# JacdacRgbLedRing8_37.net
KiCad netlist of a schematic drawn in Altium Designer
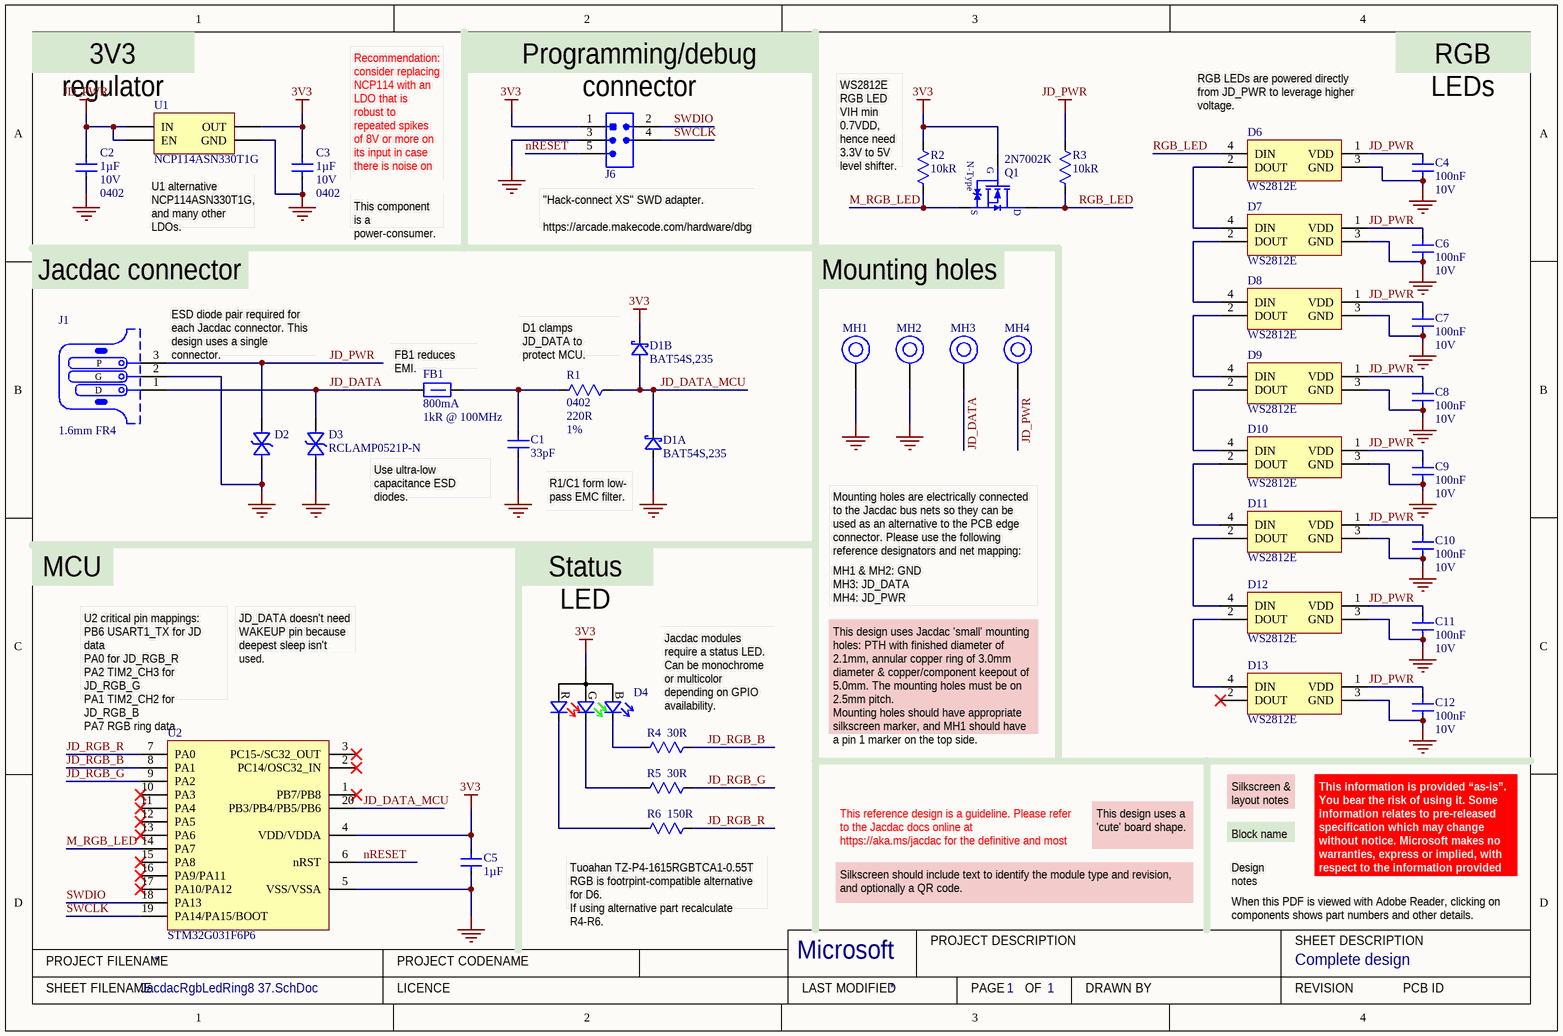
[diagram p0: JacdacRgbLedRing8 37.SchDoc]

(export (version "E")
  (design (tool "Eeschema 10.0.6"))
  (components
    (comp (ref "C1")
      (value "CL05C330JB51PNC")
      (footprint "C0402_0.55MM - without outline")
      (description "CAP CER 33PF 50V NP0 0402")
      (fields
        (field (name "MANUFACTURER") "Samsung")
        (field (name "TOLERANCE") "5%")
        (field (name "CAPACITANCE") "33pF")
        (field (name "CHECKED") "?")
        (field (name "CREATED") "DG")
      )
      (libsource (lib "Samsung") (part "CL05C330JB51PNC"))
    )
    (comp (ref "C2")
      (value "CL05A105KP5NNNC")
      (footprint "C0402_0.55MM - without outline")
      (description "CAP CER 1UF 10V X5R 0402")
      (fields
        (field (name "MANUFACTURER") "Samsung")
        (field (name "TOLERANCE") "10%")
        (field (name "CAPACITANCE") "1µF")
        (field (name "VOLTAGE RATING") "10V")
        (field (name "CASE CODE (IMPERIAL)") "0402")
        (field (name "CREATED") "DG")
        (field (name "CHECKED") "?")
      )
      (libsource (lib "Samsung") (part "CL05A105KP5NNNC"))
    )
    (comp (ref "C3")
      (value "CL05A105KP5NNNC")
      (footprint "C0402_0.55MM - without outline")
      (description "CAP CER 1UF 10V X5R 0402")
      (fields
        (field (name "MANUFACTURER") "Samsung")
        (field (name "TOLERANCE") "10%")
        (field (name "CAPACITANCE") "1µF")
        (field (name "VOLTAGE RATING") "10V")
        (field (name "CASE CODE (IMPERIAL)") "0402")
        (field (name "CREATED") "DG")
        (field (name "CHECKED") "?")
      )
      (libsource (lib "Samsung") (part "CL05A105KP5NNNC"))
    )
    (comp (ref "C4")
      (value "CL05B104KP5NNNC")
      (footprint "C0402_0.55MM - without outline")
      (description "CAP CER 0.1UF 10V X7R 0402")
      (fields
        (field (name "MANUFACTURER") "Samsung")
        (field (name "CAPACITANCE") "100nF")
        (field (name "TOLERANCE") "10%")
        (field (name "VOLTAGE RATING") "10V")
        (field (name "CREATED") "DG")
        (field (name "CHECKED") "?")
      )
      (libsource (lib "Samsung") (part "CL05B104KP5NNNC"))
    )
    (comp (ref "C5")
      (value "CL05A105KP5NNNC")
      (footprint "C0402_0.55MM - without outline")
      (description "CAP CER 1UF 10V X5R 0402")
      (fields
        (field (name "MANUFACTURER") "Samsung")
        (field (name "TOLERANCE") "10%")
        (field (name "CAPACITANCE") "1µF")
        (field (name "CREATED") "DG")
        (field (name "CHECKED") "?")
      )
      (libsource (lib "Samsung") (part "CL05A105KP5NNNC"))
    )
    (comp (ref "C6")
      (value "CL05B104KP5NNNC")
      (footprint "C0402_0.55MM - without outline")
      (description "CAP CER 0.1UF 10V X7R 0402")
      (fields
        (field (name "MANUFACTURER") "Samsung")
        (field (name "CAPACITANCE") "100nF")
        (field (name "TOLERANCE") "10%")
        (field (name "VOLTAGE RATING") "10V")
        (field (name "CREATED") "DG")
        (field (name "CHECKED") "?")
      )
      (libsource (lib "Samsung") (part "CL05B104KP5NNNC"))
    )
    (comp (ref "C7")
      (value "CL05B104KP5NNNC")
      (footprint "C0402_0.55MM - without outline")
      (description "CAP CER 0.1UF 10V X7R 0402")
      (fields
        (field (name "MANUFACTURER") "Samsung")
        (field (name "CAPACITANCE") "100nF")
        (field (name "TOLERANCE") "10%")
        (field (name "VOLTAGE RATING") "10V")
        (field (name "CREATED") "DG")
        (field (name "CHECKED") "?")
      )
      (libsource (lib "Samsung") (part "CL05B104KP5NNNC"))
    )
    (comp (ref "C8")
      (value "CL05B104KP5NNNC")
      (footprint "C0402_0.55MM - without outline")
      (description "CAP CER 0.1UF 10V X7R 0402")
      (fields
        (field (name "MANUFACTURER") "Samsung")
        (field (name "CAPACITANCE") "100nF")
        (field (name "TOLERANCE") "10%")
        (field (name "VOLTAGE RATING") "10V")
        (field (name "CREATED") "DG")
        (field (name "CHECKED") "?")
      )
      (libsource (lib "Samsung") (part "CL05B104KP5NNNC"))
    )
    (comp (ref "C9")
      (value "CL05B104KP5NNNC")
      (footprint "C0402_0.55MM - without outline")
      (description "CAP CER 0.1UF 10V X7R 0402")
      (fields
        (field (name "MANUFACTURER") "Samsung")
        (field (name "CAPACITANCE") "100nF")
        (field (name "TOLERANCE") "10%")
        (field (name "VOLTAGE RATING") "10V")
        (field (name "CREATED") "DG")
        (field (name "CHECKED") "?")
      )
      (libsource (lib "Samsung") (part "CL05B104KP5NNNC"))
    )
    (comp (ref "C10")
      (value "CL05B104KP5NNNC")
      (footprint "C0402_0.55MM - without outline")
      (description "CAP CER 0.1UF 10V X7R 0402")
      (fields
        (field (name "MANUFACTURER") "Samsung")
        (field (name "CAPACITANCE") "100nF")
        (field (name "TOLERANCE") "10%")
        (field (name "VOLTAGE RATING") "10V")
        (field (name "CREATED") "DG")
        (field (name "CHECKED") "?")
      )
      (libsource (lib "Samsung") (part "CL05B104KP5NNNC"))
    )
    (comp (ref "C11")
      (value "CL05B104KP5NNNC")
      (footprint "C0402_0.55MM - without outline")
      (description "CAP CER 0.1UF 10V X7R 0402")
      (fields
        (field (name "MANUFACTURER") "Samsung")
        (field (name "CAPACITANCE") "100nF")
        (field (name "TOLERANCE") "10%")
        (field (name "VOLTAGE RATING") "10V")
        (field (name "CREATED") "DG")
        (field (name "CHECKED") "?")
      )
      (libsource (lib "Samsung") (part "CL05B104KP5NNNC"))
    )
    (comp (ref "C12")
      (value "CL05B104KP5NNNC")
      (footprint "C0402_0.55MM - without outline")
      (description "CAP CER 0.1UF 10V X7R 0402")
      (fields
        (field (name "MANUFACTURER") "Samsung")
        (field (name "CAPACITANCE") "100nF")
        (field (name "TOLERANCE") "10%")
        (field (name "VOLTAGE RATING") "10V")
        (field (name "CREATED") "DG")
        (field (name "CHECKED") "?")
      )
      (libsource (lib "Samsung") (part "CL05B104KP5NNNC"))
    )
    (comp (ref "D1")
      (value "BAT54S")
      (footprint "NXP-BAT54S-TO-236AB - without outline")
      (description "DIODE ARRAY SCHOTTKY 30V SOT23")
      (fields (field (name "MANUFACTURER") "Nexperia") (field (name "MANUFACTURER PART NUMBER") "BAT54S,235"))
      (libsource (lib "NXP") (part "BAT54S"))
    )
    (comp (ref "D2")
      (value "RCLAMP0521P-N")
      (footprint "TVS 0402 - L")
      (description "Bidirectional 5V (Max) 6V 16V 3.5A (8/20us) 0402 TVS RoHS")
      (fields
        (field (name "MANUFACTURER") "Born Semiconductor")
        (field (name "CREATED BY") "D Gakure")
        (field (name "CHECKED BY") "?")
      )
      (libsource (lib "BornSemiconductor") (part "RCLAMP0521P-N"))
    )
    (comp (ref "D3")
      (value "RCLAMP0521P-N")
      (footprint "TVS 0402 - L")
      (description "Bidirectional 5V (Max) 6V 16V 3.5A (8/20us) 0402 TVS RoHS")
      (fields
        (field (name "MANUFACTURER") "Born Semiconductor")
        (field (name "MANUFACTURER PART NUMBER") "RCLAMP0521P-N")
        (field (name "CREATED BY") "D Gakure")
        (field (name "CHECKED BY") "?")
      )
      (libsource (lib "BornSemiconductor") (part "RCLAMP0521P-N"))
    )
    (comp (ref "D4")
      (value "TZ-P4-1615RGBTCA1-0.55T")
      (footprint "TZ-P4-1615RGBTCA1-0.55T")
      (description "1615 Light Emitting Diodes (LED) RoHS")
      (fields
        (field (name "MANUFACTURER") "TUOZHAN")
        (field (name "CREATED BY") "D. Gakure")
        (field (name "CHECKED BY") "?")
      )
      (libsource (lib "Tuozhan") (part "TZ-P4-1615RGBTCA1-0.55T"))
    )
    (comp (ref "D6")
      (value "WS2812E")
      (footprint "WS2812E-5050")
      (description "WS2812E 5050 RGB LED WITH INTEGRATED DRIVER")
      (fields (field (name "MANUFACTURER") "Worldsemi") (field (name "MANUFACTURER PART NUMBER") "WS2812E"))
      (libsource (lib "WorldSemi") (part "WS2812E-5050"))
    )
    (comp (ref "D7")
      (value "WS2812E")
      (footprint "WS2812E-5050")
      (description "WS2812E 5050 RGB LED WITH INTEGRATED DRIVER")
      (fields (field (name "MANUFACTURER") "Worldsemi") (field (name "MANUFACTURER PART NUMBER") "WS2812E"))
      (libsource (lib "WorldSemi") (part "WS2812E-5050"))
    )
    (comp (ref "D8")
      (value "WS2812E")
      (footprint "WS2812E-5050")
      (description "WS2812E 5050 RGB LED WITH INTEGRATED DRIVER")
      (fields (field (name "MANUFACTURER") "Worldsemi") (field (name "MANUFACTURER PART NUMBER") "WS2812E"))
      (libsource (lib "WorldSemi") (part "WS2812E-5050"))
    )
    (comp (ref "D9")
      (value "WS2812E")
      (footprint "WS2812E-5050")
      (description "WS2812E 5050 RGB LED WITH INTEGRATED DRIVER")
      (fields (field (name "MANUFACTURER") "Worldsemi") (field (name "MANUFACTURER PART NUMBER") "WS2812E"))
      (libsource (lib "WorldSemi") (part "WS2812E-5050"))
    )
    (comp (ref "D10")
      (value "WS2812E")
      (footprint "WS2812E-5050")
      (description "WS2812E 5050 RGB LED WITH INTEGRATED DRIVER")
      (fields (field (name "MANUFACTURER") "Worldsemi") (field (name "MANUFACTURER PART NUMBER") "WS2812E"))
      (libsource (lib "WorldSemi") (part "WS2812E-5050"))
    )
    (comp (ref "D11")
      (value "WS2812E")
      (footprint "WS2812E-5050")
      (description "WS2812E 5050 RGB LED WITH INTEGRATED DRIVER")
      (fields (field (name "MANUFACTURER") "Worldsemi") (field (name "MANUFACTURER PART NUMBER") "WS2812E"))
      (libsource (lib "WorldSemi") (part "WS2812E-5050"))
    )
    (comp (ref "D12")
      (value "WS2812E")
      (footprint "WS2812E-5050")
      (description "WS2812E 5050 RGB LED WITH INTEGRATED DRIVER")
      (fields (field (name "MANUFACTURER") "Worldsemi") (field (name "MANUFACTURER PART NUMBER") "WS2812E"))
      (libsource (lib "WorldSemi") (part "WS2812E-5050"))
    )
    (comp (ref "D13")
      (value "WS2812E")
      (footprint "WS2812E-5050")
      (description "WS2812E 5050 RGB LED WITH INTEGRATED DRIVER")
      (fields (field (name "MANUFACTURER") "Worldsemi") (field (name "MANUFACTURER PART NUMBER") "WS2812E"))
      (libsource (lib "WorldSemi") (part "WS2812E-5050"))
    )
    (comp (ref "FB1")
      (value "TDK MPZ1608S102ATA00")
      (footprint "TDK MPZ1608 0.8mm - without outline")
      (description "0603 1k@100MHz 0.8A chip")
      (fields
        (field (name "TOLERANCE") "25%")
        (field (name "MANUFACTURER") "TDK")
        (field (name "CURRENT RATING") "800mA")
        (field (name "IMPEDANCE") "1kR @ 100MHz")
      )
      (libsource (lib "TDK") (part "TDK MPZ1608S102ATA00"))
    )
    (comp (ref "J1")
      (value "3 pin JACDAC edge connector")
      (footprint "JACDAC_EDGE_CONNECTOR_NO_TRACES")
      (description "3 pin Jacdac edge connector 1.27mm pitch")
      (fields
        (field (name "MANUFACTURER PART NUMBER") "JACDAC_EDGE_CONNECTOR")
        (field (name "PCB TYPE") "1.6mm FR4")
        (field (name "CHECKED BY") "?")
        (field (name "CREATED BY") "D. Gakure")
      )
      (libsource (lib "generic-con") (part "Jacdac edge connector"))
    )
    (comp (ref "J6")
      (value "Hack Connect Mini 1.27 mm pitch 2-row")
      (footprint "HACK_CONNECT_MINI_5_X_1_27")
      (libsource (lib "HackConnect") (part "HACK_CONNECT_MINI"))
    )
    (comp (ref "MH1")
      (value "MH_5.0MMK_3.0MMC_2.1MMD_PTH")
      (footprint "MH_5.0MMK_3.0MMC_2.1MMD_PTH:MH_5.0MMK_3.0MMC_2.1MMD_PTH")
      (description "Mounting Hole 5.0mm keepout, 3.0mm annualar ring and 2.1mm Drill PTH")
      (libsource (lib "generic") (part "MH_5.0MMK_3.0MMC_2.1MMD_PTH"))
    )
    (comp (ref "MH2")
      (value "MH_5.0MMK_3.0MMC_2.1MMD_PTH")
      (footprint "MH_5.0MMK_3.0MMC_2.1MMD_PTH:MH_5.0MMK_3.0MMC_2.1MMD_PTH")
      (description "Mounting Hole 5.0mm keepout, 3.0mm annualar ring and 2.1mm Drill PTH")
      (libsource (lib "generic") (part "MH_5.0MMK_3.0MMC_2.1MMD_PTH"))
    )
    (comp (ref "MH3")
      (value "MH_5.0MMK_3.0MMC_2.1MMD_PTH")
      (footprint "MH_5.0MMK_3.0MMC_2.1MMD_PTH:MH_5.0MMK_3.0MMC_2.1MMD_PTH")
      (description "Mounting Hole 5.0mm keepout, 3.0mm annualar ring and 2.1mm Drill PTH")
      (libsource (lib "generic") (part "MH_5.0MMK_3.0MMC_2.1MMD_PTH"))
    )
    (comp (ref "MH4")
      (value "MH_5.0MMK_3.0MMC_2.1MMD_PTH")
      (footprint "MH_5.0MMK_3.0MMC_2.1MMD_PTH")
      (description "Mounting Hole 5.0mm keepout, 3.0mm annualar ring and 2.1mm Drill PTH")
      (libsource (lib "generic") (part "MH_5.0MMK_3.0MMC_2.1MMD_PTH"))
    )
    (comp (ref "Q1")
      (value "2N7002K")
      (footprint "SOT-23")
      (description "MOSFET Transistor, N Channel, 300 mA, 60 V, 2 ohm, 10 V, 2.5 V")
      (fields
        (field (name "MANUFACTURER") "ON Semiconductor / Fairchild")
        (field (name "VOLTAGE") "60V")
        (field (name "MANUFACTURER PART NUMBER") "2N7002K")
        (field (name "CREATED BY") "D. Gakure")
        (field (name "CHECKED BY") "?")
      )
      (libsource (lib "OnSemiconductor") (part "2N7002K (2)"))
    )
    (comp (ref "R1")
      (value "RC0402FR-07220RL")
      (footprint "R0402 - Without outline")
      (description "RES SMD 220 OHM 1% 1/16W 0402")
      (fields
        (field (name "MANUFACTURER") "Yageo")
        (field (name "CASE CODE (IMPERIAL)") "0402")
        (field (name "RESISTANCE") "220R")
        (field (name "TOLERANCE") "1%")
        (field (name "CREATED") "D.G")
        (field (name "CHECKED") "?")
      )
      (libsource (lib "Yageo") (part "RC0402FR-07220RL"))
    )
    (comp (ref "R2")
      (value "10k")
      (footprint "R0402 - Without outline")
      (description "RES SMD 10K OHM 1% 1/16W 0402")
      (fields
        (field (name "MANUFACTURER") "Yageo")
        (field (name "MANUFACTURER PART NUMBER") "RC0402FR-0710KL")
        (field (name "RESISTANCE") "10kR")
        (field (name "CHECKED") "?")
        (field (name "CREATED") "DG")
      )
      (libsource (lib "Yageo") (part "RC0402FR-0710KL"))
    )
    (comp (ref "R3")
      (value "10k")
      (footprint "R0402 - Without outline")
      (description "RES SMD 10K OHM 1% 1/16W 0402")
      (fields
        (field (name "MANUFACTURER") "Yageo")
        (field (name "MANUFACTURER PART NUMBER") "RC0402FR-0710KL")
        (field (name "RESISTANCE") "10kR")
        (field (name "CHECKED") "?")
        (field (name "CREATED") "DG")
      )
      (libsource (lib "Yageo") (part "RC0402FR-0710KL"))
    )
    (comp (ref "R4")
      (value "RC0402FR-0730RL")
      (footprint "R0402 - Without outline")
      (description "RES SMD 30 OHM 1% 1/16W 0402")
      (fields
        (field (name "MANUFACTURER") "Yageo")
        (field (name "RESISTANCE") "30R")
        (field (name "TOLERANCE") "1%")
        (field (name "CREATED BY") "D. Gakure")
        (field (name "CHECKED BY") "?")
      )
      (libsource (lib "Yageo") (part "RC0402FR-0730RL"))
    )
    (comp (ref "R5")
      (value "RC0402FR-0730RL")
      (footprint "R0402 - Without outline")
      (description "RES SMD 30 OHM 1% 1/16W 0402")
      (fields
        (field (name "MANUFACTURER") "Yageo")
        (field (name "RESISTANCE") "30R")
        (field (name "TOLERANCE") "1%")
        (field (name "CREATED BY") "D. Gakure")
        (field (name "CHECKED BY") "?")
      )
      (libsource (lib "Yageo") (part "RC0402FR-0730RL"))
    )
    (comp (ref "R6")
      (value "RC0402FR-07150RL")
      (footprint "R0402 - Without outline")
      (description "RES SMD 150 OHM 1% 1/16W 0402")
      (fields
        (field (name "MANUFACTURER") "Yageo")
        (field (name "RESISTANCE") "150R")
        (field (name "TOLERANCE") "1%")
        (field (name "CREATED BY") "D. Gakure")
        (field (name "CHECKED BY") "?")
      )
      (libsource (lib "Yageo") (part "RC0402FR-07150RL"))
    )
    (comp (ref "U1")
      (value "LDO 3.3V/300 mA")
      (footprint "ON_SEMI-SOT23-5 - without outline")
      (fields
        (field (name "MANUFACTURER") "ON Semiconductor")
        (field (name "MANUFACTURER PART NUMBER") "NCP114ASN330T1G")
        (field (name "CREATED") "DG")
        (field (name "CHECKED") "?")
      )
      (libsource (lib "OnSemiconductor") (part "NCP114ASN330T1G"))
    )
    (comp (ref "U2")
      (value "STM32G031F6P6")
      (footprint "20-TSSOP")
      (description "MCU 32-Bit STM32G031 ARM Cortex-M0+ RISC 32KB Flash 1.7V to 3.6V 20-Pin TSSOP Tube")
      (fields
        (field (name "MANUFACTURER") "STMicroelectronics")
        (field (name "MANUFACTURER PART NUMBER") "STM32G031F6P6")
        (field (name "CREATED BY") "D. Gakure")
        (field (name "CHECKED BY") "?")
      )
      (libsource (lib "ST") (part "STM32G031F6P6"))
    )
  )
  (nets
    (net (code "1") (name "/JD_DATA") (class "Default")
      (node (ref "D3") (pin "1") (pinfunction "K_1") (pintype "passive"))
      (node (ref "FB1") (pin "1") (pinfunction "1_1") (pintype "passive"))
      (node (ref "J1") (pin "1") (pinfunction "D_1") (pintype "passive"))
      (node (ref "MH3") (pin "1") (pinfunction "1_1") (pintype "passive"))
    )
    (net (code "2") (name "/JD_DATA_MCU") (class "Default")
      (node (ref "D1") (pin "3") (pinfunction "K_3") (pintype "passive"))
      (node (ref "R1") (pin "1") (pinfunction "1_1") (pintype "passive"))
      (node (ref "U2") (pin "20") (pinfunction "PB3/PB4/PB5/PB6_20") (pintype "power_in"))
    )
    (net (code "3") (name "/JD_RGB_B") (class "Default")
      (node (ref "R4") (pin "2") (pinfunction "2_2") (pintype "passive"))
      (node (ref "U2") (pin "8") (pinfunction "PA1_8") (pintype "passive"))
    )
    (net (code "4") (name "/JD_RGB_G") (class "Default")
      (node (ref "R5") (pin "2") (pinfunction "2_2") (pintype "passive"))
      (node (ref "U2") (pin "9") (pinfunction "PA2_9") (pintype "passive"))
    )
    (net (code "5") (name "/JD_RGB_R") (class "Default")
      (node (ref "R6") (pin "2") (pinfunction "2_2") (pintype "passive"))
      (node (ref "U2") (pin "7") (pinfunction "PA0_7") (pintype "passive"))
    )
    (net (code "6") (name "/M_RGB_LED") (class "Default")
      (node (ref "Q1") (pin "2") (pinfunction "S_2") (pintype "passive"))
      (node (ref "R2") (pin "2") (pinfunction "2_2") (pintype "passive"))
      (node (ref "U2") (pin "14") (pinfunction "PA7_14") (pintype "passive"))
    )
    (net (code "7") (name "/RGB_LED") (class "Default")
      (node (ref "D6") (pin "4") (pinfunction "DIN_4") (pintype "passive"))
      (node (ref "Q1") (pin "3") (pinfunction "D_3") (pintype "passive"))
      (node (ref "R3") (pin "2") (pinfunction "2_2") (pintype "passive"))
    )
    (net (code "8") (name "/SWCLK") (class "Default")
      (node (ref "J6") (pin "4") (pinfunction "SWCLK_4") (pintype "passive"))
      (node (ref "U2") (pin "19") (pinfunction "PA14/PA15/BOOT_19") (pintype "passive"))
    )
    (net (code "9") (name "/SWDIO") (class "Default")
      (node (ref "J6") (pin "2") (pinfunction "SWDIO_2") (pintype "passive"))
      (node (ref "U2") (pin "18") (pinfunction "PA13_18") (pintype "passive"))
    )
    (net (code "10") (name "/nRESET") (class "Default")
      (node (ref "J6") (pin "5") (pinfunction "RESET_5") (pintype "passive"))
      (node (ref "U2") (pin "6") (pinfunction "nRST_6") (pintype "power_in"))
    )
    (net (code "11") (name "3V3") (class "Default")
      (node (ref "C3") (pin "2") (pinfunction "2_2") (pintype "passive"))
      (node (ref "C5") (pin "2") (pinfunction "2_2") (pintype "passive"))
      (node (ref "D1") (pin "2") (pinfunction "K_2") (pintype "passive"))
      (node (ref "D4") (pin "1") (pinfunction "A_1") (pintype "passive"))
      (node (ref "J6") (pin "1") (pinfunction "VCC_1") (pintype "passive"))
      (node (ref "Q1") (pin "1") (pinfunction "G_1") (pintype "passive"))
      (node (ref "R2") (pin "1") (pinfunction "1_1") (pintype "passive"))
      (node (ref "U1") (pin "5") (pinfunction "OUT_5") (pintype "passive"))
      (node (ref "U2") (pin "4") (pinfunction "VDD/VDDA_4") (pintype "passive"))
    )
    (net (code "12") (name "GND") (class "Default")
      (node (ref "C1") (pin "1") (pinfunction "1_1") (pintype "passive"))
      (node (ref "C10") (pin "1") (pinfunction "1_1") (pintype "passive"))
      (node (ref "C11") (pin "1") (pinfunction "1_1") (pintype "passive"))
      (node (ref "C12") (pin "1") (pinfunction "1_1") (pintype "passive"))
      (node (ref "C2") (pin "1") (pinfunction "1_1") (pintype "passive"))
      (node (ref "C3") (pin "1") (pinfunction "1_1") (pintype "passive"))
      (node (ref "C4") (pin "1") (pinfunction "1_1") (pintype "passive"))
      (node (ref "C5") (pin "1") (pinfunction "1_1") (pintype "passive"))
      (node (ref "C6") (pin "1") (pinfunction "1_1") (pintype "passive"))
      (node (ref "C7") (pin "1") (pinfunction "1_1") (pintype "passive"))
      (node (ref "C8") (pin "1") (pinfunction "1_1") (pintype "passive"))
      (node (ref "C9") (pin "1") (pinfunction "1_1") (pintype "passive"))
      (node (ref "D1") (pin "1") (pinfunction "A_1") (pintype "passive"))
      (node (ref "D10") (pin "3") (pinfunction "GND_3") (pintype "passive"))
      (node (ref "D11") (pin "3") (pinfunction "GND_3") (pintype "passive"))
      (node (ref "D12") (pin "3") (pinfunction "GND_3") (pintype "passive"))
      (node (ref "D13") (pin "3") (pinfunction "GND_3") (pintype "passive"))
      (node (ref "D2") (pin "2") (pinfunction "A_2") (pintype "passive"))
      (node (ref "D3") (pin "2") (pinfunction "A_2") (pintype "passive"))
      (node (ref "D6") (pin "3") (pinfunction "GND_3") (pintype "passive"))
      (node (ref "D7") (pin "3") (pinfunction "GND_3") (pintype "passive"))
      (node (ref "D8") (pin "3") (pinfunction "GND_3") (pintype "passive"))
      (node (ref "D9") (pin "3") (pinfunction "GND_3") (pintype "passive"))
      (node (ref "J1") (pin "2") (pinfunction "G_2") (pintype "passive"))
      (node (ref "J6") (pin "3") (pinfunction "GND_3") (pintype "passive"))
      (node (ref "MH1") (pin "1") (pinfunction "1_1") (pintype "passive"))
      (node (ref "MH2") (pin "1") (pinfunction "1_1") (pintype "passive"))
      (node (ref "U1") (pin "2") (pinfunction "GND_2") (pintype "passive"))
      (node (ref "U2") (pin "5") (pinfunction "VSS/VSSA_5") (pintype "power_in"))
    )
    (net (code "13") (name "JD_PWR") (class "Default")
      (node (ref "C10") (pin "2") (pinfunction "2_2") (pintype "passive"))
      (node (ref "C11") (pin "2") (pinfunction "2_2") (pintype "passive"))
      (node (ref "C12") (pin "2") (pinfunction "2_2") (pintype "passive"))
      (node (ref "C2") (pin "2") (pinfunction "2_2") (pintype "passive"))
      (node (ref "C4") (pin "2") (pinfunction "2_2") (pintype "passive"))
      (node (ref "C6") (pin "2") (pinfunction "2_2") (pintype "passive"))
      (node (ref "C7") (pin "2") (pinfunction "2_2") (pintype "passive"))
      (node (ref "C8") (pin "2") (pinfunction "2_2") (pintype "passive"))
      (node (ref "C9") (pin "2") (pinfunction "2_2") (pintype "passive"))
      (node (ref "D10") (pin "1") (pinfunction "VDD_1") (pintype "passive"))
      (node (ref "D11") (pin "1") (pinfunction "VDD_1") (pintype "passive"))
      (node (ref "D12") (pin "1") (pinfunction "VDD_1") (pintype "passive"))
      (node (ref "D13") (pin "1") (pinfunction "VDD_1") (pintype "passive"))
      (node (ref "D2") (pin "1") (pinfunction "K_1") (pintype "passive"))
      (node (ref "D6") (pin "1") (pinfunction "VDD_1") (pintype "passive"))
      (node (ref "D7") (pin "1") (pinfunction "VDD_1") (pintype "passive"))
      (node (ref "D8") (pin "1") (pinfunction "VDD_1") (pintype "passive"))
      (node (ref "D9") (pin "1") (pinfunction "VDD_1") (pintype "passive"))
      (node (ref "J1") (pin "3") (pinfunction "P_3") (pintype "passive"))
      (node (ref "MH4") (pin "1") (pinfunction "1_1") (pintype "passive"))
      (node (ref "R3") (pin "1") (pinfunction "1_1") (pintype "passive"))
      (node (ref "U1") (pin "1") (pinfunction "IN_1") (pintype "passive"))
      (node (ref "U1") (pin "3") (pinfunction "EN_3") (pintype "passive"))
    )
    (net (code "14") (name "Net-(C1-Pad2)") (class "Default")
      (node (ref "C1") (pin "2") (pinfunction "2_2") (pintype "passive"))
      (node (ref "FB1") (pin "2") (pinfunction "2_2") (pintype "passive"))
      (node (ref "R1") (pin "2") (pinfunction "2_2") (pintype "passive"))
    )
    (net (code "15") (name "Net-(D4-B)") (class "Default")
      (node (ref "D4") (pin "4") (pinfunction "B_4") (pintype "passive"))
      (node (ref "R4") (pin "1") (pinfunction "1_1") (pintype "passive"))
    )
    (net (code "16") (name "Net-(D4-G)") (class "Default")
      (node (ref "D4") (pin "3") (pinfunction "G_3") (pintype "passive"))
      (node (ref "R5") (pin "1") (pinfunction "1_1") (pintype "passive"))
    )
    (net (code "17") (name "Net-(D4-R)") (class "Default")
      (node (ref "D4") (pin "2") (pinfunction "R_2") (pintype "passive"))
      (node (ref "R6") (pin "1") (pinfunction "1_1") (pintype "passive"))
    )
    (net (code "18") (name "Net-(D6-DOUT)") (class "Default")
      (node (ref "D6") (pin "2") (pinfunction "DOUT_2") (pintype "passive"))
      (node (ref "D7") (pin "4") (pinfunction "DIN_4") (pintype "passive"))
    )
    (net (code "19") (name "Net-(D7-DOUT)") (class "Default")
      (node (ref "D7") (pin "2") (pinfunction "DOUT_2") (pintype "passive"))
      (node (ref "D8") (pin "4") (pinfunction "DIN_4") (pintype "passive"))
    )
    (net (code "20") (name "Net-(D8-DOUT)") (class "Default")
      (node (ref "D8") (pin "2") (pinfunction "DOUT_2") (pintype "passive"))
      (node (ref "D9") (pin "4") (pinfunction "DIN_4") (pintype "passive"))
    )
    (net (code "21") (name "Net-(D10-DIN)") (class "Default")
      (node (ref "D10") (pin "4") (pinfunction "DIN_4") (pintype "passive"))
      (node (ref "D9") (pin "2") (pinfunction "DOUT_2") (pintype "passive"))
    )
    (net (code "22") (name "Net-(D10-DOUT)") (class "Default")
      (node (ref "D10") (pin "2") (pinfunction "DOUT_2") (pintype "passive"))
      (node (ref "D11") (pin "4") (pinfunction "DIN_4") (pintype "passive"))
    )
    (net (code "23") (name "Net-(D11-DOUT)") (class "Default")
      (node (ref "D11") (pin "2") (pinfunction "DOUT_2") (pintype "passive"))
      (node (ref "D12") (pin "4") (pinfunction "DIN_4") (pintype "passive"))
    )
    (net (code "24") (name "Net-(D12-DOUT)") (class "Default")
      (node (ref "D12") (pin "2") (pinfunction "DOUT_2") (pintype "passive"))
      (node (ref "D13") (pin "4") (pinfunction "DIN_4") (pintype "passive"))
    )
    (net (code "25") (name "unconnected-(D13-DOUT-Pad2)") (class "Default")
      (node (ref "D13") (pin "2") (pinfunction "DOUT_2") (pintype "passive+no_connect"))
    )
    (net (code "26") (name "unconnected-(U2-PA3-Pad10)") (class "Default")
      (node (ref "U2") (pin "10") (pinfunction "PA3_10") (pintype "passive+no_connect"))
    )
    (net (code "27") (name "unconnected-(U2-PA4-Pad11)") (class "Default")
      (node (ref "U2") (pin "11") (pinfunction "PA4_11") (pintype "passive+no_connect"))
    )
    (net (code "28") (name "unconnected-(U2-PA5-Pad12)") (class "Default")
      (node (ref "U2") (pin "12") (pinfunction "PA5_12") (pintype "passive+no_connect"))
    )
    (net (code "29") (name "unconnected-(U2-PA6-Pad13)") (class "Default")
      (node (ref "U2") (pin "13") (pinfunction "PA6_13") (pintype "passive+no_connect"))
    )
    (net (code "30") (name "unconnected-(U2-PA8-Pad15)") (class "Default")
      (node (ref "U2") (pin "15") (pinfunction "PA8_15") (pintype "passive+no_connect"))
    )
    (net (code "31") (name "unconnected-(U2-PA9{slash}PA11-Pad16)") (class "Default")
      (node (ref "U2") (pin "16") (pinfunction "PA9/PA11_16") (pintype "passive+no_connect"))
    )
    (net (code "32") (name "unconnected-(U2-PA10{slash}PA12-Pad17)") (class "Default")
      (node (ref "U2") (pin "17") (pinfunction "PA10/PA12_17") (pintype "passive+no_connect"))
    )
    (net (code "33") (name "unconnected-(U2-PB7{slash}PB8-Pad1)") (class "Default")
      (node (ref "U2") (pin "1") (pinfunction "PB7/PB8_1") (pintype "passive+no_connect"))
    )
    (net (code "34") (name "unconnected-(U2-PC14{slash}OSC32_IN-Pad2)") (class "Default")
      (node (ref "U2") (pin "2") (pinfunction "PC14/OSC32_IN_2") (pintype "passive+no_connect"))
    )
    (net (code "35") (name "unconnected-(U2-PC15-{slash}SC32_OUT-Pad3)") (class "Default")
      (node (ref "U2") (pin "3") (pinfunction "PC15-/SC32_OUT_3") (pintype "passive+no_connect"))
    )
  )
)
